# WSN_Gateway_v4_1.net
KiCad netlist of a schematic drawn in EAGLE
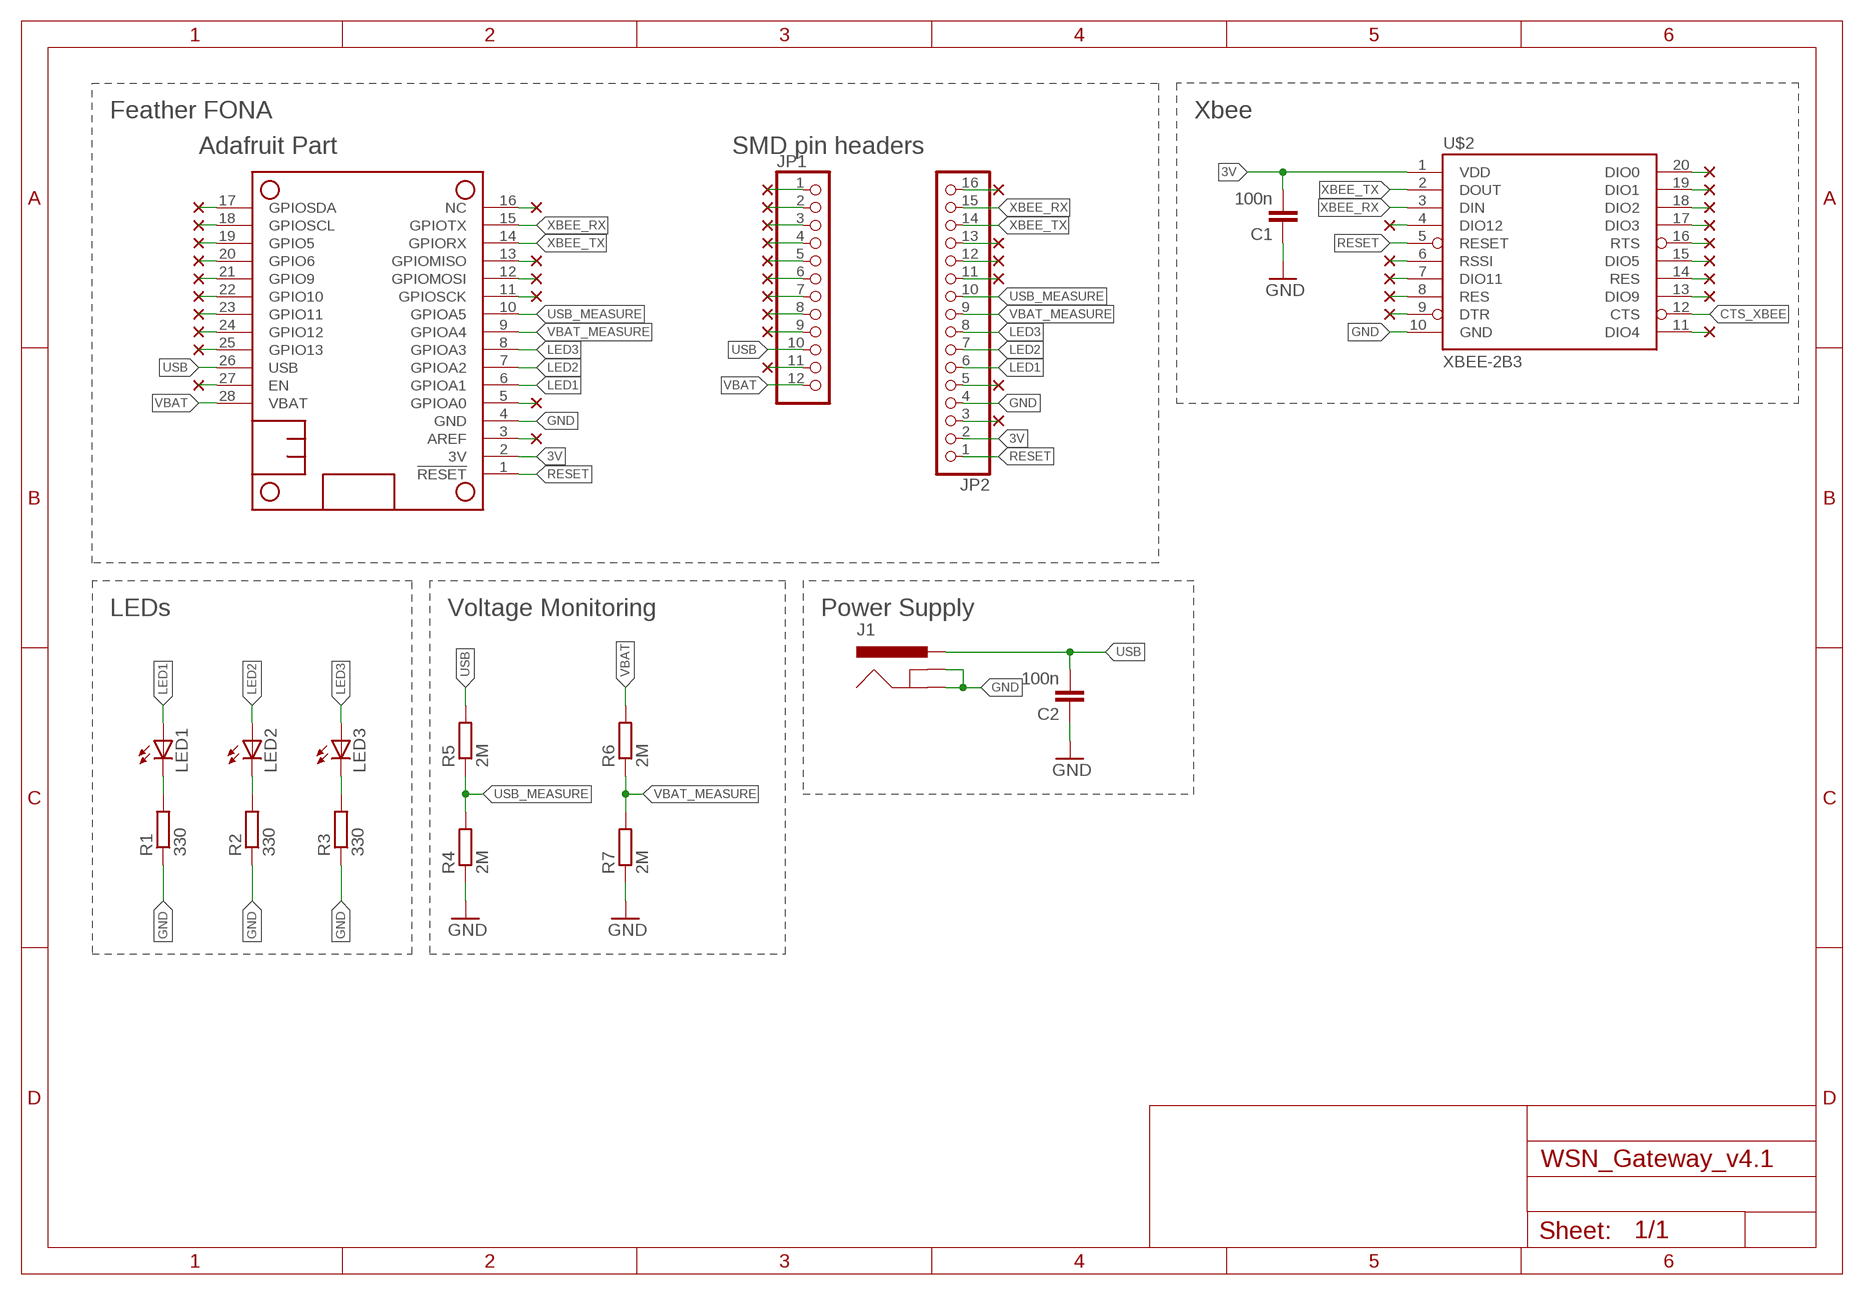
[diagram p0: schematic, sheet 1]

(export (version "E")
  (design (tool "Eeschema 10.0.6"))
  (components
    (comp (ref "C1")
      (value "100n")
      (footprint "eagle-import:C0805")
      (libsource (lib "eagle-import") (part "C"))
    )
    (comp (ref "C2")
      (value "100n")
      (footprint "eagle-import:C0805")
      (libsource (lib "eagle-import") (part "C"))
    )
    (comp (ref "J1")
      (value "5.5x2.1mm Barrel")
      (footprint "eagle-import:POWER_JACK_SMD")
      (libsource (lib "eagle-import") (part "POWER_JACKSMD"))
    )
    (comp (ref "JP1")
      (value "PINHD-1X121X12_SMT")
      (footprint "eagle-import:1X12_SMT")
      (libsource (lib "eagle-import") (part "PINHD-1X121X12_SMT"))
    )
    (comp (ref "JP2")
      (value "PINHD-1X161X16_SMT")
      (footprint "eagle-import:1X16_SMT")
      (libsource (lib "eagle-import") (part "PINHD-1X161X16_SMT"))
    )
    (comp (ref "LED1")
      (value "LEDCHIPLED_0805")
      (footprint "eagle-import:CHIPLED_0805")
      (libsource (lib "eagle-import") (part "LEDCHIPLED_0805"))
    )
    (comp (ref "LED2")
      (value "LEDCHIPLED_0805")
      (footprint "eagle-import:CHIPLED_0805")
      (libsource (lib "eagle-import") (part "LEDCHIPLED_0805"))
    )
    (comp (ref "LED3")
      (value "LEDCHIPLED_0805")
      (footprint "eagle-import:CHIPLED_0805")
      (libsource (lib "eagle-import") (part "LEDCHIPLED_0805"))
    )
    (comp (ref "MS1")
      (value "FEATHERWING_NODIM_NOHOLES")
      (footprint "eagle-import:FEATHERWING_DIM_2")
      (libsource (lib "eagle-import") (part "FEATHERWING_NODIM_NOHOLES"))
    )
    (comp (ref "R1")
      (value "330")
      (footprint "eagle-import:R0805")
      (libsource (lib "eagle-import") (part "R-EU_R0805"))
    )
    (comp (ref "R2")
      (value "330")
      (footprint "eagle-import:R0805")
      (libsource (lib "eagle-import") (part "R-EU_R0805"))
    )
    (comp (ref "R3")
      (value "330")
      (footprint "eagle-import:R0805")
      (libsource (lib "eagle-import") (part "R-EU_R0805"))
    )
    (comp (ref "R4")
      (value "2M")
      (footprint "eagle-import:R0805")
      (libsource (lib "eagle-import") (part "R-EU_R0805"))
    )
    (comp (ref "R5")
      (value "2M")
      (footprint "eagle-import:R0805")
      (libsource (lib "eagle-import") (part "R-EU_R0805"))
    )
    (comp (ref "R6")
      (value "2M")
      (footprint "eagle-import:R0805")
      (libsource (lib "eagle-import") (part "R-EU_R0805"))
    )
    (comp (ref "R7")
      (value "2M")
      (footprint "eagle-import:R0805")
      (libsource (lib "eagle-import") (part "R-EU_R0805"))
    )
    (comp (ref "U$2")
      (value "XBEE-2B3")
      (footprint "eagle-import:XBEE-SMD")
      (libsource (lib "eagle-import") (part "XBEE-2B3"))
    )
  )
  (nets
    (net (code "1") (name "3V") (class "Default")
      (node (ref "C1") (pin "2") (pinfunction "2_2") (pintype "passive"))
      (node (ref "JP2") (pin "2") (pinfunction "2_2") (pintype "passive"))
      (node (ref "MS1") (pin "2") (pinfunction "3V_2") (pintype "power_in"))
      (node (ref "U$2") (pin "1") (pinfunction "VDD_1") (pintype "power_in"))
    )
    (net (code "2") (name "CTS_XBEE") (class "Default")
      (node (ref "U$2") (pin "12") (pinfunction "CTS_12") (pintype "output"))
    )
    (net (code "3") (name "GND") (class "Default")
      (node (ref "C1") (pin "1") (pinfunction "1_1") (pintype "passive"))
      (node (ref "C2") (pin "1") (pinfunction "1_1") (pintype "passive"))
      (node (ref "J1") (pin "GND") (pinfunction "GNDBREAK_GND") (pintype "bidirectional"))
      (node (ref "J1") (pin "P$4") (pinfunction "GND_P$4") (pintype "bidirectional"))
      (node (ref "JP2") (pin "4") (pinfunction "4_4") (pintype "passive"))
      (node (ref "MS1") (pin "4") (pinfunction "GND_4") (pintype "power_in"))
      (node (ref "R1") (pin "1") (pinfunction "1_1") (pintype "passive"))
      (node (ref "R2") (pin "1") (pinfunction "1_1") (pintype "passive"))
      (node (ref "R3") (pin "1") (pinfunction "1_1") (pintype "passive"))
      (node (ref "R4") (pin "1") (pinfunction "1_1") (pintype "passive"))
      (node (ref "R7") (pin "1") (pinfunction "1_1") (pintype "passive"))
      (node (ref "U$2") (pin "10") (pinfunction "GND_10") (pintype "power_in"))
    )
    (net (code "4") (name "LED1") (class "Default")
      (node (ref "JP2") (pin "6") (pinfunction "6_6") (pintype "passive"))
      (node (ref "LED1") (pin "A") (pinfunction "A_A") (pintype "passive"))
      (node (ref "MS1") (pin "6") (pinfunction "GPIOA1_6") (pintype "bidirectional"))
    )
    (net (code "5") (name "LED2") (class "Default")
      (node (ref "JP2") (pin "7") (pinfunction "7_7") (pintype "passive"))
      (node (ref "LED2") (pin "A") (pinfunction "A_A") (pintype "passive"))
      (node (ref "MS1") (pin "7") (pinfunction "GPIOA2_7") (pintype "bidirectional"))
    )
    (net (code "6") (name "LED3") (class "Default")
      (node (ref "JP2") (pin "8") (pinfunction "8_8") (pintype "passive"))
      (node (ref "LED3") (pin "A") (pinfunction "A_A") (pintype "passive"))
      (node (ref "MS1") (pin "8") (pinfunction "GPIOA3_8") (pintype "bidirectional"))
    )
    (net (code "7") (name "Net-(LED1-PadC)") (class "Default")
      (node (ref "LED1") (pin "C") (pinfunction "C_C") (pintype "passive"))
      (node (ref "R1") (pin "2") (pinfunction "2_2") (pintype "passive"))
    )
    (net (code "8") (name "Net-(LED2-PadC)") (class "Default")
      (node (ref "LED2") (pin "C") (pinfunction "C_C") (pintype "passive"))
      (node (ref "R2") (pin "2") (pinfunction "2_2") (pintype "passive"))
    )
    (net (code "9") (name "Net-(LED3-PadC)") (class "Default")
      (node (ref "LED3") (pin "C") (pinfunction "C_C") (pintype "passive"))
      (node (ref "R3") (pin "2") (pinfunction "2_2") (pintype "passive"))
    )
    (net (code "10") (name "RESET") (class "Default")
      (node (ref "JP2") (pin "1") (pinfunction "1_1") (pintype "passive"))
      (node (ref "MS1") (pin "1") (pinfunction "~{RESET}_1") (pintype "input"))
      (node (ref "U$2") (pin "5") (pinfunction "RESET_5") (pintype "input"))
    )
    (net (code "11") (name "USB") (class "Default")
      (node (ref "C2") (pin "2") (pinfunction "2_2") (pintype "passive"))
      (node (ref "J1") (pin "VIN0") (pinfunction "PWR_VIN0") (pintype "bidirectional"))
      (node (ref "J1") (pin "VIN1") (pinfunction "PWR_VIN1") (pintype "bidirectional"))
      (node (ref "JP1") (pin "10") (pinfunction "10_10") (pintype "passive"))
      (node (ref "MS1") (pin "26") (pinfunction "USB_26") (pintype "power_in"))
      (node (ref "R5") (pin "2") (pinfunction "2_2") (pintype "passive"))
    )
    (net (code "12") (name "USB_MEASURE") (class "Default")
      (node (ref "JP2") (pin "10") (pinfunction "10_10") (pintype "passive"))
      (node (ref "MS1") (pin "10") (pinfunction "GPIOA5_10") (pintype "bidirectional"))
      (node (ref "R4") (pin "2") (pinfunction "2_2") (pintype "passive"))
      (node (ref "R5") (pin "1") (pinfunction "1_1") (pintype "passive"))
    )
    (net (code "13") (name "VBAT") (class "Default")
      (node (ref "JP1") (pin "12") (pinfunction "12_12") (pintype "passive"))
      (node (ref "MS1") (pin "28") (pinfunction "VBAT_28") (pintype "power_in"))
      (node (ref "R6") (pin "2") (pinfunction "2_2") (pintype "passive"))
    )
    (net (code "14") (name "VBAT_MEASURE") (class "Default")
      (node (ref "JP2") (pin "9") (pinfunction "9_9") (pintype "passive"))
      (node (ref "MS1") (pin "9") (pinfunction "GPIOA4_9") (pintype "bidirectional"))
      (node (ref "R6") (pin "1") (pinfunction "1_1") (pintype "passive"))
      (node (ref "R7") (pin "2") (pinfunction "2_2") (pintype "passive"))
    )
    (net (code "15") (name "XBEE_RX") (class "Default")
      (node (ref "JP2") (pin "15") (pinfunction "15_15") (pintype "passive"))
      (node (ref "MS1") (pin "15") (pinfunction "GPIOTX_15") (pintype "bidirectional"))
      (node (ref "U$2") (pin "3") (pinfunction "DIN_3") (pintype "input"))
    )
    (net (code "16") (name "XBEE_TX") (class "Default")
      (node (ref "JP2") (pin "14") (pinfunction "14_14") (pintype "passive"))
      (node (ref "MS1") (pin "14") (pinfunction "GPIORX_14") (pintype "bidirectional"))
      (node (ref "U$2") (pin "2") (pinfunction "DOUT_2") (pintype "output"))
    )
    (net (code "17") (name "unconnected-(JP1-Pad1)") (class "Default")
      (node (ref "JP1") (pin "1") (pinfunction "1_1") (pintype "passive"))
    )
    (net (code "18") (name "unconnected-(JP1-Pad2)") (class "Default")
      (node (ref "JP1") (pin "2") (pinfunction "2_2") (pintype "passive"))
    )
    (net (code "19") (name "unconnected-(JP1-Pad3)") (class "Default")
      (node (ref "JP1") (pin "3") (pinfunction "3_3") (pintype "passive"))
    )
    (net (code "20") (name "unconnected-(JP1-Pad4)") (class "Default")
      (node (ref "JP1") (pin "4") (pinfunction "4_4") (pintype "passive"))
    )
    (net (code "21") (name "unconnected-(JP1-Pad5)") (class "Default")
      (node (ref "JP1") (pin "5") (pinfunction "5_5") (pintype "passive"))
    )
    (net (code "22") (name "unconnected-(JP1-Pad6)") (class "Default")
      (node (ref "JP1") (pin "6") (pinfunction "6_6") (pintype "passive"))
    )
    (net (code "23") (name "unconnected-(JP1-Pad7)") (class "Default")
      (node (ref "JP1") (pin "7") (pinfunction "7_7") (pintype "passive"))
    )
    (net (code "24") (name "unconnected-(JP1-Pad8)") (class "Default")
      (node (ref "JP1") (pin "8") (pinfunction "8_8") (pintype "passive"))
    )
    (net (code "25") (name "unconnected-(JP1-Pad9)") (class "Default")
      (node (ref "JP1") (pin "9") (pinfunction "9_9") (pintype "passive"))
    )
    (net (code "26") (name "unconnected-(JP1-Pad11)") (class "Default")
      (node (ref "JP1") (pin "11") (pinfunction "11_11") (pintype "passive"))
    )
    (net (code "27") (name "unconnected-(JP2-Pad3)") (class "Default")
      (node (ref "JP2") (pin "3") (pinfunction "3_3") (pintype "passive"))
    )
    (net (code "28") (name "unconnected-(JP2-Pad5)") (class "Default")
      (node (ref "JP2") (pin "5") (pinfunction "5_5") (pintype "passive"))
    )
    (net (code "29") (name "unconnected-(JP2-Pad11)") (class "Default")
      (node (ref "JP2") (pin "11") (pinfunction "11_11") (pintype "passive"))
    )
    (net (code "30") (name "unconnected-(JP2-Pad12)") (class "Default")
      (node (ref "JP2") (pin "12") (pinfunction "12_12") (pintype "passive"))
    )
    (net (code "31") (name "unconnected-(JP2-Pad13)") (class "Default")
      (node (ref "JP2") (pin "13") (pinfunction "13_13") (pintype "passive"))
    )
    (net (code "32") (name "unconnected-(JP2-Pad16)") (class "Default")
      (node (ref "JP2") (pin "16") (pinfunction "16_16") (pintype "passive"))
    )
    (net (code "33") (name "unconnected-(MS1-AREF-Pad3)") (class "Default")
      (node (ref "MS1") (pin "3") (pinfunction "AREF_3") (pintype "passive"))
    )
    (net (code "34") (name "unconnected-(MS1-EN-Pad27)") (class "Default")
      (node (ref "MS1") (pin "27") (pinfunction "EN_27") (pintype "passive"))
    )
    (net (code "35") (name "unconnected-(MS1-GPIO5-Pad19)") (class "Default")
      (node (ref "MS1") (pin "19") (pinfunction "GPIO5_19") (pintype "bidirectional"))
    )
    (net (code "36") (name "unconnected-(MS1-GPIO6-Pad20)") (class "Default")
      (node (ref "MS1") (pin "20") (pinfunction "GPIO6_20") (pintype "bidirectional"))
    )
    (net (code "37") (name "unconnected-(MS1-GPIO9-Pad21)") (class "Default")
      (node (ref "MS1") (pin "21") (pinfunction "GPIO9_21") (pintype "bidirectional"))
    )
    (net (code "38") (name "unconnected-(MS1-GPIO10-Pad22)") (class "Default")
      (node (ref "MS1") (pin "22") (pinfunction "GPIO10_22") (pintype "bidirectional"))
    )
    (net (code "39") (name "unconnected-(MS1-GPIO11-Pad23)") (class "Default")
      (node (ref "MS1") (pin "23") (pinfunction "GPIO11_23") (pintype "bidirectional"))
    )
    (net (code "40") (name "unconnected-(MS1-GPIO12-Pad24)") (class "Default")
      (node (ref "MS1") (pin "24") (pinfunction "GPIO12_24") (pintype "bidirectional"))
    )
    (net (code "41") (name "unconnected-(MS1-GPIO13-Pad25)") (class "Default")
      (node (ref "MS1") (pin "25") (pinfunction "GPIO13_25") (pintype "bidirectional"))
    )
    (net (code "42") (name "unconnected-(MS1-GPIOA0-Pad5)") (class "Default")
      (node (ref "MS1") (pin "5") (pinfunction "GPIOA0_5") (pintype "bidirectional"))
    )
    (net (code "43") (name "unconnected-(MS1-GPIOMISO-Pad13)") (class "Default")
      (node (ref "MS1") (pin "13") (pinfunction "GPIOMISO_13") (pintype "bidirectional"))
    )
    (net (code "44") (name "unconnected-(MS1-GPIOMOSI-Pad12)") (class "Default")
      (node (ref "MS1") (pin "12") (pinfunction "GPIOMOSI_12") (pintype "bidirectional"))
    )
    (net (code "45") (name "unconnected-(MS1-GPIOSCK-Pad11)") (class "Default")
      (node (ref "MS1") (pin "11") (pinfunction "GPIOSCK_11") (pintype "bidirectional"))
    )
    (net (code "46") (name "unconnected-(MS1-GPIOSCL-Pad18)") (class "Default")
      (node (ref "MS1") (pin "18") (pinfunction "GPIOSCL_18") (pintype "bidirectional"))
    )
    (net (code "47") (name "unconnected-(MS1-GPIOSDA-Pad17)") (class "Default")
      (node (ref "MS1") (pin "17") (pinfunction "GPIOSDA_17") (pintype "bidirectional"))
    )
    (net (code "48") (name "unconnected-(MS1-NC-Pad16)") (class "Default")
      (node (ref "MS1") (pin "16") (pinfunction "NC_16") (pintype "passive"))
    )
    (net (code "49") (name "unconnected-(U$2-DIO0-Pad20)") (class "Default")
      (node (ref "U$2") (pin "20") (pinfunction "DIO0_20") (pintype "bidirectional"))
    )
    (net (code "50") (name "unconnected-(U$2-DIO1-Pad19)") (class "Default")
      (node (ref "U$2") (pin "19") (pinfunction "DIO1_19") (pintype "bidirectional"))
    )
    (net (code "51") (name "unconnected-(U$2-DIO2-Pad18)") (class "Default")
      (node (ref "U$2") (pin "18") (pinfunction "DIO2_18") (pintype "bidirectional"))
    )
    (net (code "52") (name "unconnected-(U$2-DIO3-Pad17)") (class "Default")
      (node (ref "U$2") (pin "17") (pinfunction "DIO3_17") (pintype "bidirectional"))
    )
    (net (code "53") (name "unconnected-(U$2-DIO4-Pad11)") (class "Default")
      (node (ref "U$2") (pin "11") (pinfunction "DIO4_11") (pintype "bidirectional"))
    )
    (net (code "54") (name "unconnected-(U$2-DIO5-Pad15)") (class "Default")
      (node (ref "U$2") (pin "15") (pinfunction "DIO5_15") (pintype "bidirectional"))
    )
    (net (code "55") (name "unconnected-(U$2-DIO9-Pad13)") (class "Default")
      (node (ref "U$2") (pin "13") (pinfunction "DIO9_13") (pintype "bidirectional"))
    )
    (net (code "56") (name "unconnected-(U$2-DIO11-Pad7)") (class "Default")
      (node (ref "U$2") (pin "7") (pinfunction "DIO11_7") (pintype "bidirectional"))
    )
    (net (code "57") (name "unconnected-(U$2-DIO12-Pad4)") (class "Default")
      (node (ref "U$2") (pin "4") (pinfunction "DIO12_4") (pintype "bidirectional"))
    )
    (net (code "58") (name "unconnected-(U$2-DTR-Pad9)") (class "Default")
      (node (ref "U$2") (pin "9") (pinfunction "DTR_9") (pintype "bidirectional"))
    )
    (net (code "59") (name "unconnected-(U$2-RES-Pad8)") (class "Default")
      (node (ref "U$2") (pin "8") (pinfunction "RES_8") (pintype "bidirectional"))
    )
    (net (code "60") (name "unconnected-(U$2-RES-Pad14)") (class "Default")
      (node (ref "U$2") (pin "14") (pinfunction "RES_14") (pintype "bidirectional"))
    )
    (net (code "61") (name "unconnected-(U$2-RSSI-Pad6)") (class "Default")
      (node (ref "U$2") (pin "6") (pinfunction "RSSI_6") (pintype "bidirectional"))
    )
    (net (code "62") (name "unconnected-(U$2-RTS-Pad16)") (class "Default")
      (node (ref "U$2") (pin "16") (pinfunction "RTS_16") (pintype "input"))
    )
  )
)
